# dsky_md_4_0v.net
KiCad netlist of a schematic drawn in EAGLE
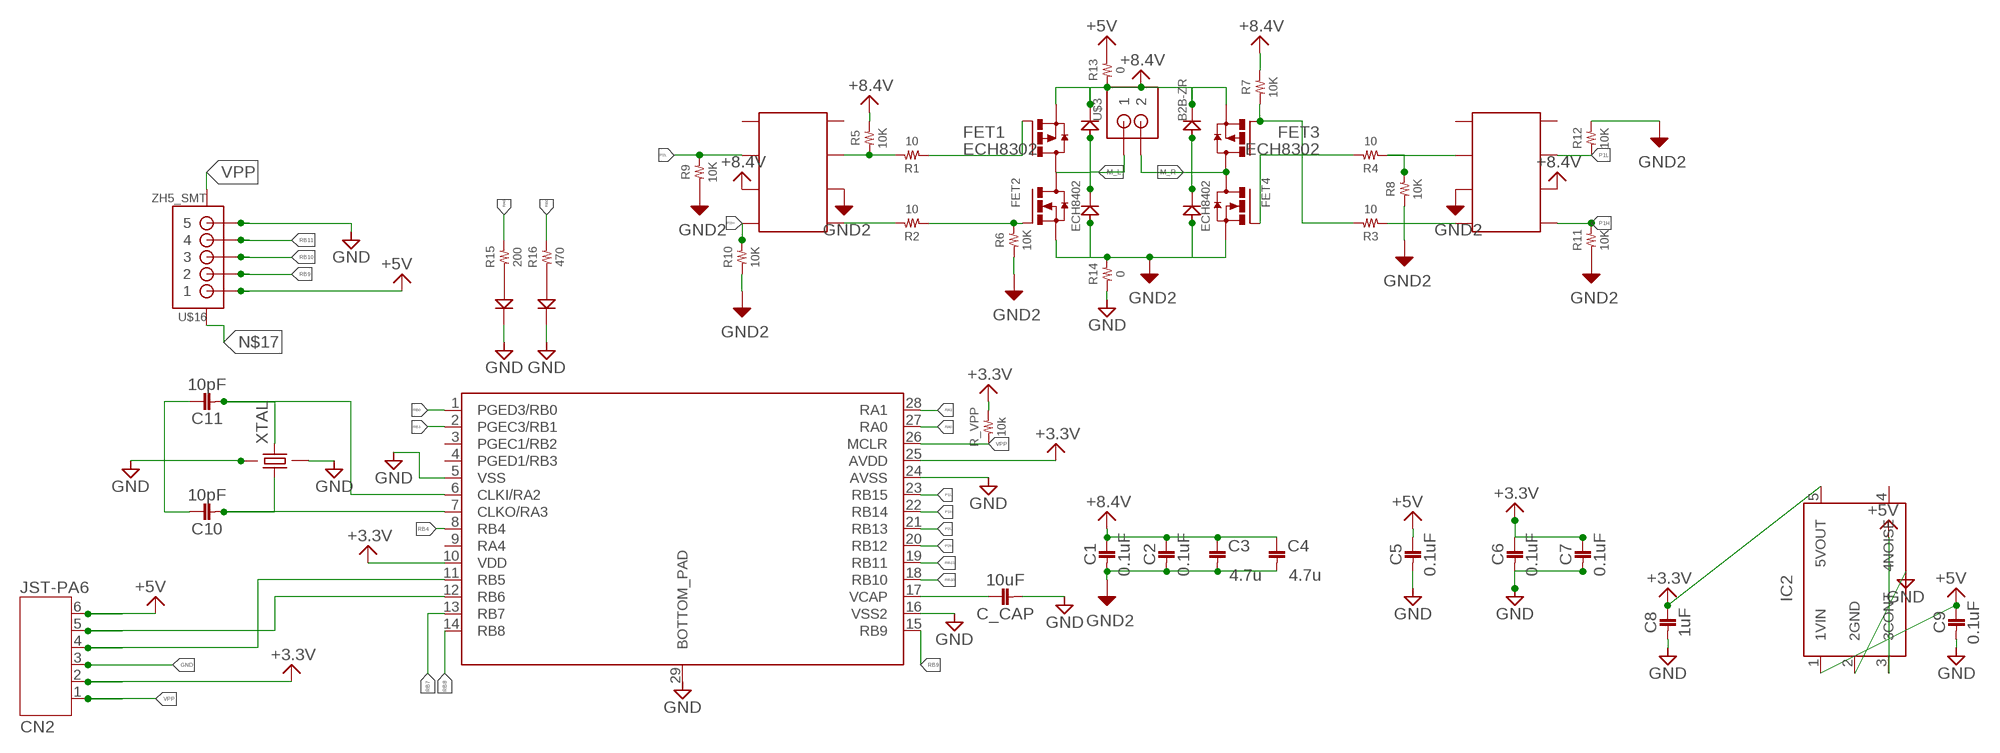
[diagram p0: schematic, sheet 1]

(export (version "E")
  (design (tool "Eeschema 10.0.6"))
  (components
    (comp (ref "C1")
      (value "0.1uF")
      (footprint "eagle-import:1608")
      (libsource (lib "eagle-import") (part "1608"))
    )
    (comp (ref "C2")
      (value "0.1uF")
      (footprint "eagle-import:1608")
      (libsource (lib "eagle-import") (part "1608"))
    )
    (comp (ref "C3")
      (value "4.7u")
      (footprint "eagle-import:2012")
      (libsource (lib "eagle-import") (part "2012"))
    )
    (comp (ref "C4")
      (value "4.7u")
      (footprint "eagle-import:2012")
      (libsource (lib "eagle-import") (part "2012"))
    )
    (comp (ref "C5")
      (value "0.1uF")
      (footprint "eagle-import:1608")
      (libsource (lib "eagle-import") (part "1608"))
    )
    (comp (ref "C6")
      (value "0.1uF")
      (footprint "eagle-import:1608")
      (libsource (lib "eagle-import") (part "1608"))
    )
    (comp (ref "C7")
      (value "0.1uF")
      (footprint "eagle-import:1608")
      (libsource (lib "eagle-import") (part "1608"))
    )
    (comp (ref "C8")
      (value "1uF")
      (footprint "eagle-import:1608")
      (libsource (lib "eagle-import") (part "1608"))
    )
    (comp (ref "C9")
      (value "0.1uF")
      (footprint "eagle-import:1608")
      (libsource (lib "eagle-import") (part "1608"))
    )
    (comp (ref "C10")
      (value "10pF")
      (footprint "eagle-import:1608")
      (libsource (lib "eagle-import") (part "1608"))
    )
    (comp (ref "C11")
      (value "10pF")
      (footprint "eagle-import:1608")
      (libsource (lib "eagle-import") (part "1608"))
    )
    (comp (ref "CN2")
      (value "JST-PA6")
      (footprint "eagle-import:JST-PA6")
      (libsource (lib "eagle-import") (part "JST-PA6"))
    )
    (comp (ref "C_CAP")
      (value "10uF")
      (footprint "eagle-import:1608")
      (libsource (lib "eagle-import") (part "1608"))
    )
    (comp (ref "D1")
      (value "SS2040")
      (footprint "eagle-import:SOD-123FL")
      (libsource (lib "eagle-import") (part "SS2040"))
    )
    (comp (ref "D2")
      (value "SS2040")
      (footprint "eagle-import:SOD-123FL")
      (libsource (lib "eagle-import") (part "SS2040"))
    )
    (comp (ref "D3")
      (value "SS2040")
      (footprint "eagle-import:SOD-123FL")
      (libsource (lib "eagle-import") (part "SS2040"))
    )
    (comp (ref "D4")
      (value "SS2040")
      (footprint "eagle-import:SOD-123FL")
      (libsource (lib "eagle-import") (part "SS2040"))
    )
    (comp (ref "FET1")
      (value "ECH8302")
      (footprint "eagle-import:ECH8")
      (libsource (lib "eagle-import") (part "ECH83"))
    )
    (comp (ref "FET2")
      (value "ECH8402")
      (footprint "eagle-import:ECH8")
      (libsource (lib "eagle-import") (part "ECH84"))
    )
    (comp (ref "FET3")
      (value "ECH8302")
      (footprint "eagle-import:ECH8")
      (libsource (lib "eagle-import") (part "ECH83"))
    )
    (comp (ref "FET4")
      (value "ECH8402")
      (footprint "eagle-import:ECH8")
      (libsource (lib "eagle-import") (part "ECH84"))
    )
    (comp (ref "IC1")
      (value "DSPIC33EP32MC202")
      (footprint "eagle-import:QFN-S28_6X6MC")
      (libsource (lib "eagle-import") (part "DSPIC33EP32MC202"))
    )
    (comp (ref "IC2")
      (value "NJM2866F33")
      (footprint "eagle-import:SSOP5-P-0.95")
      (libsource (lib "eagle-import") (part "TAR5SB"))
    )
    (comp (ref "IC3")
      (value "TC1427COA")
      (footprint "eagle-import:SOIC8")
      (libsource (lib "eagle-import") (part "TC1427COA"))
    )
    (comp (ref "IC4")
      (value "TC1427COA")
      (footprint "eagle-import:SOIC8")
      (libsource (lib "eagle-import") (part "TC1427COA"))
    )
    (comp (ref "LED1")
      (value "1608")
      (footprint "eagle-import:1608")
      (libsource (lib "eagle-import") (part "10_LED_1608"))
    )
    (comp (ref "LED2")
      (value "1608")
      (footprint "eagle-import:1608")
      (libsource (lib "eagle-import") (part "10_LED_1608"))
    )
    (comp (ref "R1")
      (value "10")
      (footprint "eagle-import:1608")
      (libsource (lib "eagle-import") (part "RESISTOR__SMD"))
    )
    (comp (ref "R2")
      (value "10")
      (footprint "eagle-import:1608")
      (libsource (lib "eagle-import") (part "RESISTOR__SMD"))
    )
    (comp (ref "R3")
      (value "10")
      (footprint "eagle-import:1608")
      (libsource (lib "eagle-import") (part "RESISTOR__SMD"))
    )
    (comp (ref "R4")
      (value "10")
      (footprint "eagle-import:1608")
      (libsource (lib "eagle-import") (part "RESISTOR__SMD"))
    )
    (comp (ref "R5")
      (value "10K")
      (footprint "eagle-import:1608")
      (libsource (lib "eagle-import") (part "RESISTOR__SMD"))
    )
    (comp (ref "R6")
      (value "10K")
      (footprint "eagle-import:1608")
      (libsource (lib "eagle-import") (part "RESISTOR__SMD"))
    )
    (comp (ref "R7")
      (value "10K")
      (footprint "eagle-import:1608")
      (libsource (lib "eagle-import") (part "RESISTOR__SMD"))
    )
    (comp (ref "R8")
      (value "10K")
      (footprint "eagle-import:1608")
      (libsource (lib "eagle-import") (part "RESISTOR__SMD"))
    )
    (comp (ref "R9")
      (value "10K")
      (footprint "eagle-import:1608")
      (libsource (lib "eagle-import") (part "RESISTOR__SMD"))
    )
    (comp (ref "R10")
      (value "10K")
      (footprint "eagle-import:1608")
      (libsource (lib "eagle-import") (part "RESISTOR__SMD"))
    )
    (comp (ref "R11")
      (value "10K")
      (footprint "eagle-import:1608")
      (libsource (lib "eagle-import") (part "RESISTOR__SMD"))
    )
    (comp (ref "R12")
      (value "10K")
      (footprint "eagle-import:1608")
      (libsource (lib "eagle-import") (part "RESISTOR__SMD"))
    )
    (comp (ref "R13")
      (value "0")
      (footprint "eagle-import:1608")
      (libsource (lib "eagle-import") (part "RESISTOR__SMD"))
    )
    (comp (ref "R14")
      (value "0")
      (footprint "eagle-import:1608")
      (libsource (lib "eagle-import") (part "RESISTOR__SMD"))
    )
    (comp (ref "R15")
      (value "200")
      (footprint "eagle-import:1608")
      (libsource (lib "eagle-import") (part "RESISTOR__SMD"))
    )
    (comp (ref "R16")
      (value "470")
      (footprint "eagle-import:1608")
      (libsource (lib "eagle-import") (part "RESISTOR__SMD"))
    )
    (comp (ref "R_VPP")
      (value "10k")
      (footprint "eagle-import:1608")
      (libsource (lib "eagle-import") (part "RESISTOR__SMD"))
    )
    (comp (ref "U$3")
      (value "B2B-ZR")
      (footprint "eagle-import:B2B-ZR")
      (libsource (lib "eagle-import") (part "B2B-ZR"))
    )
    (comp (ref "U$16")
      (value "ZH5_SMT")
      (footprint "eagle-import:ZH5_SMT")
      (libsource (lib "eagle-import") (part "ZH5_SMT"))
    )
    (comp (ref "XTAL")
      (value "X22")
      (footprint "eagle-import:SMD_X22")
      (libsource (lib "eagle-import") (part "X22"))
    )
  )
  (nets
    (net (code "1") (name "+3.3V") (class "Default")
      (node (ref "C6") (pin "P$1") (pinfunction "1_P$1") (pintype "passive"))
      (node (ref "C7") (pin "P$1") (pinfunction "1_P$1") (pintype "passive"))
      (node (ref "C8") (pin "P$1") (pinfunction "1_P$1") (pintype "passive"))
      (node (ref "CN2") (pin "2") (pinfunction "2_2") (pintype "passive"))
      (node (ref "IC1") (pin "10") (pinfunction "VDD_10") (pintype "bidirectional"))
      (node (ref "IC1") (pin "25") (pinfunction "AVDD_25") (pintype "bidirectional"))
      (node (ref "IC2") (pin "5") (pinfunction "5VOUT_5") (pintype "bidirectional"))
      (node (ref "R_VPP") (pin "2") (pinfunction "P$2_2") (pintype "passive"))
    )
    (net (code "2") (name "+5V") (class "Default")
      (node (ref "C5") (pin "P$1") (pinfunction "1_P$1") (pintype "passive"))
      (node (ref "C9") (pin "P$1") (pinfunction "1_P$1") (pintype "passive"))
      (node (ref "CN2") (pin "6") (pinfunction "6_6") (pintype "passive"))
      (node (ref "IC2") (pin "1") (pinfunction "1VIN_1") (pintype "bidirectional"))
      (node (ref "IC2") (pin "3") (pinfunction "3CONT_3") (pintype "bidirectional"))
      (node (ref "R13") (pin "2") (pinfunction "P$2_2") (pintype "passive"))
      (node (ref "U$16") (pin "P1") (pinfunction "1_P1") (pintype "bidirectional"))
    )
    (net (code "3") (name "+8.4V") (class "Default")
      (node (ref "C1") (pin "P$1") (pinfunction "1_P$1") (pintype "passive"))
      (node (ref "C2") (pin "P$1") (pinfunction "1_P$1") (pintype "passive"))
      (node (ref "C3") (pin "1") (pinfunction "1_1") (pintype "passive"))
      (node (ref "C4") (pin "1") (pinfunction "1_1") (pintype "passive"))
      (node (ref "D1") (pin "2") (pinfunction "PK_2") (pintype "bidirectional"))
      (node (ref "D3") (pin "2") (pinfunction "PK_2") (pintype "bidirectional"))
      (node (ref "FET1") (pin "1") (pinfunction "S_1") (pintype "passive"))
      (node (ref "FET1") (pin "2") (pinfunction "S_2") (pintype "passive"))
      (node (ref "FET1") (pin "3") (pinfunction "S_3") (pintype "passive"))
      (node (ref "FET3") (pin "1") (pinfunction "S_1") (pintype "passive"))
      (node (ref "FET3") (pin "2") (pinfunction "S_2") (pintype "passive"))
      (node (ref "FET3") (pin "3") (pinfunction "S_3") (pintype "passive"))
      (node (ref "IC3") (pin "3") (pinfunction "3_GND_3") (pintype "bidirectional"))
      (node (ref "IC4") (pin "3") (pinfunction "3_GND_3") (pintype "bidirectional"))
      (node (ref "R13") (pin "1") (pinfunction "P$1_1") (pintype "passive"))
      (node (ref "R5") (pin "2") (pinfunction "P$2_2") (pintype "passive"))
      (node (ref "R7") (pin "2") (pinfunction "P$2_2") (pintype "passive"))
    )
    (net (code "4") (name "GND") (class "Default")
      (node (ref "C10") (pin "P$1") (pinfunction "1_P$1") (pintype "passive"))
      (node (ref "C11") (pin "P$1") (pinfunction "1_P$1") (pintype "passive"))
      (node (ref "C5") (pin "P$2") (pinfunction "2_P$2") (pintype "passive"))
      (node (ref "C6") (pin "P$2") (pinfunction "2_P$2") (pintype "passive"))
      (node (ref "C7") (pin "P$2") (pinfunction "2_P$2") (pintype "passive"))
      (node (ref "C8") (pin "P$2") (pinfunction "2_P$2") (pintype "passive"))
      (node (ref "C9") (pin "P$2") (pinfunction "2_P$2") (pintype "passive"))
      (node (ref "CN2") (pin "3") (pinfunction "3_3") (pintype "passive"))
      (node (ref "C_CAP") (pin "P$2") (pinfunction "2_P$2") (pintype "passive"))
      (node (ref "IC1") (pin "16") (pinfunction "VSS2_16") (pintype "power_in"))
      (node (ref "IC1") (pin "24") (pinfunction "AVSS_24") (pintype "bidirectional"))
      (node (ref "IC1") (pin "29") (pinfunction "BOTTOM_PAD_29") (pintype "bidirectional"))
      (node (ref "IC1") (pin "5") (pinfunction "VSS_5") (pintype "power_in"))
      (node (ref "IC2") (pin "2") (pinfunction "2GND_2") (pintype "bidirectional"))
      (node (ref "LED1") (pin "2") (pinfunction "K_2") (pintype "bidirectional"))
      (node (ref "LED2") (pin "2") (pinfunction "K_2") (pintype "bidirectional"))
      (node (ref "R14") (pin "1") (pinfunction "P$1_1") (pintype "passive"))
      (node (ref "U$16") (pin "P5") (pinfunction "5_P5") (pintype "bidirectional"))
      (node (ref "XTAL") (pin "2") (pinfunction "2_2") (pintype "bidirectional"))
      (node (ref "XTAL") (pin "4") (pinfunction "4_4") (pintype "bidirectional"))
    )
    (net (code "5") (name "GND2") (class "Default")
      (node (ref "C1") (pin "P$2") (pinfunction "2_P$2") (pintype "passive"))
      (node (ref "C2") (pin "P$2") (pinfunction "2_P$2") (pintype "passive"))
      (node (ref "C3") (pin "2") (pinfunction "2_2") (pintype "passive"))
      (node (ref "C4") (pin "2") (pinfunction "2_2") (pintype "passive"))
      (node (ref "D2") (pin "1") (pinfunction "PA_1") (pintype "bidirectional"))
      (node (ref "D4") (pin "1") (pinfunction "PA_1") (pintype "bidirectional"))
      (node (ref "FET2") (pin "1") (pinfunction "S_1") (pintype "passive"))
      (node (ref "FET2") (pin "2") (pinfunction "S_2") (pintype "passive"))
      (node (ref "FET2") (pin "3") (pinfunction "S_3") (pintype "passive"))
      (node (ref "FET4") (pin "1") (pinfunction "S_1") (pintype "passive"))
      (node (ref "FET4") (pin "2") (pinfunction "S_2") (pintype "passive"))
      (node (ref "FET4") (pin "3") (pinfunction "S_3") (pintype "passive"))
      (node (ref "IC3") (pin "6") (pinfunction "6_VDD_6") (pintype "bidirectional"))
      (node (ref "IC4") (pin "6") (pinfunction "6_VDD_6") (pintype "bidirectional"))
      (node (ref "R10") (pin "1") (pinfunction "P$1_1") (pintype "passive"))
      (node (ref "R11") (pin "1") (pinfunction "P$1_1") (pintype "passive"))
      (node (ref "R12") (pin "2") (pinfunction "P$2_2") (pintype "passive"))
      (node (ref "R14") (pin "2") (pinfunction "P$2_2") (pintype "passive"))
      (node (ref "R6") (pin "1") (pinfunction "P$1_1") (pintype "passive"))
      (node (ref "R8") (pin "1") (pinfunction "P$1_1") (pintype "passive"))
      (node (ref "R9") (pin "1") (pinfunction "P$1_1") (pintype "passive"))
    )
    (net (code "6") (name "M_L") (class "Default")
      (node (ref "D1") (pin "1") (pinfunction "PA_1") (pintype "bidirectional"))
      (node (ref "D2") (pin "2") (pinfunction "PK_2") (pintype "bidirectional"))
      (node (ref "FET1") (pin "5") (pinfunction "D_5") (pintype "passive"))
      (node (ref "FET1") (pin "6") (pinfunction "D_6") (pintype "passive"))
      (node (ref "FET1") (pin "7") (pinfunction "D_7") (pintype "passive"))
      (node (ref "FET1") (pin "8") (pinfunction "D_8") (pintype "passive"))
      (node (ref "FET2") (pin "5") (pinfunction "D_5") (pintype "passive"))
      (node (ref "FET2") (pin "6") (pinfunction "D_6") (pintype "passive"))
      (node (ref "FET2") (pin "7") (pinfunction "D_7") (pintype "passive"))
      (node (ref "FET2") (pin "8") (pinfunction "D_8") (pintype "passive"))
      (node (ref "U$3") (pin "1") (pinfunction "1_1") (pintype "bidirectional"))
    )
    (net (code "7") (name "M_R") (class "Default")
      (node (ref "D3") (pin "1") (pinfunction "PA_1") (pintype "bidirectional"))
      (node (ref "D4") (pin "2") (pinfunction "PK_2") (pintype "bidirectional"))
      (node (ref "FET3") (pin "5") (pinfunction "D_5") (pintype "passive"))
      (node (ref "FET3") (pin "6") (pinfunction "D_6") (pintype "passive"))
      (node (ref "FET3") (pin "7") (pinfunction "D_7") (pintype "passive"))
      (node (ref "FET3") (pin "8") (pinfunction "D_8") (pintype "passive"))
      (node (ref "FET4") (pin "5") (pinfunction "D_5") (pintype "passive"))
      (node (ref "FET4") (pin "6") (pinfunction "D_6") (pintype "passive"))
      (node (ref "FET4") (pin "7") (pinfunction "D_7") (pintype "passive"))
      (node (ref "FET4") (pin "8") (pinfunction "D_8") (pintype "passive"))
      (node (ref "U$3") (pin "2") (pinfunction "2_2") (pintype "bidirectional"))
    )
    (net (code "8") (name "N$17") (class "Default")
      (node (ref "U$16") (pin "G1") (pinfunction "G_L_G1") (pintype "bidirectional"))
    )
    (net (code "9") (name "Net-(C10-2)") (class "Default")
      (node (ref "C10") (pin "P$2") (pinfunction "2_P$2") (pintype "passive"))
      (node (ref "IC1") (pin "7") (pinfunction "CLKO/RA3_7") (pintype "bidirectional"))
      (node (ref "XTAL") (pin "1") (pinfunction "1_1") (pintype "passive"))
    )
    (net (code "10") (name "Net-(C11-2)") (class "Default")
      (node (ref "C11") (pin "P$2") (pinfunction "2_P$2") (pintype "passive"))
      (node (ref "IC1") (pin "6") (pinfunction "CLKI/RA2_6") (pintype "bidirectional"))
      (node (ref "XTAL") (pin "3") (pinfunction "3_3") (pintype "passive"))
    )
    (net (code "11") (name "Net-(C_CAP-1)") (class "Default")
      (node (ref "C_CAP") (pin "P$1") (pinfunction "1_P$1") (pintype "passive"))
      (node (ref "IC1") (pin "17") (pinfunction "VCAP_17") (pintype "bidirectional"))
    )
    (net (code "12") (name "Net-(FET1-G)") (class "Default")
      (node (ref "FET1") (pin "4") (pinfunction "G_4") (pintype "passive"))
      (node (ref "R1") (pin "1") (pinfunction "P$1_1") (pintype "passive"))
    )
    (net (code "13") (name "Net-(FET2-G)") (class "Default")
      (node (ref "FET2") (pin "4") (pinfunction "G_4") (pintype "passive"))
      (node (ref "R2") (pin "1") (pinfunction "P$1_1") (pintype "passive"))
      (node (ref "R6") (pin "2") (pinfunction "P$2_2") (pintype "passive"))
    )
    (net (code "14") (name "Net-(FET3-G)") (class "Default")
      (node (ref "FET3") (pin "4") (pinfunction "G_4") (pintype "passive"))
      (node (ref "R3") (pin "2") (pinfunction "P$2_2") (pintype "passive"))
      (node (ref "R7") (pin "1") (pinfunction "P$1_1") (pintype "passive"))
    )
    (net (code "15") (name "Net-(FET4-G)") (class "Default")
      (node (ref "FET4") (pin "4") (pinfunction "G_4") (pintype "passive"))
      (node (ref "R4") (pin "2") (pinfunction "P$2_2") (pintype "passive"))
    )
    (net (code "16") (name "Net-(IC1-RB5)") (class "Default")
      (node (ref "CN2") (pin "4") (pinfunction "4_4") (pintype "passive"))
      (node (ref "IC1") (pin "11") (pinfunction "RB5_11") (pintype "bidirectional"))
    )
    (net (code "17") (name "Net-(IC1-RB6)") (class "Default")
      (node (ref "CN2") (pin "5") (pinfunction "5_5") (pintype "passive"))
      (node (ref "IC1") (pin "12") (pinfunction "RB6_12") (pintype "bidirectional"))
    )
    (net (code "18") (name "Net-(IC3-5_OUT_B)") (class "Default")
      (node (ref "IC3") (pin "5") (pinfunction "5_OUT_B_5") (pintype "bidirectional"))
      (node (ref "R2") (pin "2") (pinfunction "P$2_2") (pintype "passive"))
    )
    (net (code "19") (name "Net-(IC3-7_OUT_A)") (class "Default")
      (node (ref "IC3") (pin "7") (pinfunction "7_OUT_A_7") (pintype "bidirectional"))
      (node (ref "R1") (pin "2") (pinfunction "P$2_2") (pintype "passive"))
      (node (ref "R5") (pin "1") (pinfunction "P$1_1") (pintype "passive"))
    )
    (net (code "20") (name "Net-(IC4-5_OUT_B)") (class "Default")
      (node (ref "IC4") (pin "5") (pinfunction "5_OUT_B_5") (pintype "bidirectional"))
      (node (ref "R3") (pin "1") (pinfunction "P$1_1") (pintype "passive"))
    )
    (net (code "21") (name "Net-(IC4-7_OUT_A)") (class "Default")
      (node (ref "IC4") (pin "7") (pinfunction "7_OUT_A_7") (pintype "bidirectional"))
      (node (ref "R4") (pin "1") (pinfunction "P$1_1") (pintype "passive"))
      (node (ref "R8") (pin "2") (pinfunction "P$2_2") (pintype "passive"))
    )
    (net (code "22") (name "Net-(LED1-A)") (class "Default")
      (node (ref "LED1") (pin "1") (pinfunction "A_1") (pintype "bidirectional"))
      (node (ref "R15") (pin "1") (pinfunction "P$1_1") (pintype "passive"))
    )
    (net (code "23") (name "Net-(LED2-A)") (class "Default")
      (node (ref "LED2") (pin "1") (pinfunction "A_1") (pintype "bidirectional"))
      (node (ref "R16") (pin "1") (pinfunction "P$1_1") (pintype "passive"))
    )
    (net (code "24") (name "P1H") (class "Default")
      (node (ref "IC1") (pin "22") (pinfunction "RB14_22") (pintype "bidirectional"))
      (node (ref "IC4") (pin "4") (pinfunction "4_IN_B_4") (pintype "bidirectional"))
      (node (ref "R11") (pin "2") (pinfunction "P$2_2") (pintype "passive"))
    )
    (net (code "25") (name "P1L") (class "Default")
      (node (ref "IC1") (pin "23") (pinfunction "RB15_23") (pintype "bidirectional"))
      (node (ref "IC4") (pin "2") (pinfunction "2_IN_A_2") (pintype "bidirectional"))
      (node (ref "R12") (pin "1") (pinfunction "P$1_1") (pintype "passive"))
    )
    (net (code "26") (name "P2H") (class "Default")
      (node (ref "IC1") (pin "20") (pinfunction "RB12_20") (pintype "bidirectional"))
      (node (ref "IC3") (pin "4") (pinfunction "4_IN_B_4") (pintype "bidirectional"))
      (node (ref "R10") (pin "2") (pinfunction "P$2_2") (pintype "passive"))
    )
    (net (code "27") (name "P2L") (class "Default")
      (node (ref "IC1") (pin "21") (pinfunction "RB13_21") (pintype "bidirectional"))
      (node (ref "IC3") (pin "2") (pinfunction "2_IN_A_2") (pintype "bidirectional"))
      (node (ref "R9") (pin "2") (pinfunction "P$2_2") (pintype "passive"))
    )
    (net (code "28") (name "RA0") (class "Default")
      (node (ref "IC1") (pin "27") (pinfunction "RA0_27") (pintype "bidirectional"))
      (node (ref "R15") (pin "2") (pinfunction "P$2_2") (pintype "passive"))
    )
    (net (code "29") (name "RA1") (class "Default")
      (node (ref "IC1") (pin "28") (pinfunction "RA1_28") (pintype "bidirectional"))
    )
    (net (code "30") (name "RB0") (class "Default")
      (node (ref "IC1") (pin "1") (pinfunction "PGED3/RB0_1") (pintype "bidirectional"))
      (node (ref "R16") (pin "2") (pinfunction "P$2_2") (pintype "passive"))
    )
    (net (code "31") (name "RB1") (class "Default")
      (node (ref "IC1") (pin "2") (pinfunction "PGEC3/RB1_2") (pintype "bidirectional"))
    )
    (net (code "32") (name "RB4") (class "Default")
      (node (ref "IC1") (pin "8") (pinfunction "RB4_8") (pintype "bidirectional"))
    )
    (net (code "33") (name "RB7") (class "Default")
      (node (ref "IC1") (pin "13") (pinfunction "RB7_13") (pintype "bidirectional"))
    )
    (net (code "34") (name "RB8") (class "Default")
      (node (ref "IC1") (pin "14") (pinfunction "RB8_14") (pintype "bidirectional"))
    )
    (net (code "35") (name "RB9") (class "Default")
      (node (ref "IC1") (pin "15") (pinfunction "RB9_15") (pintype "bidirectional"))
      (node (ref "U$16") (pin "P2") (pinfunction "2_P2") (pintype "bidirectional"))
    )
    (net (code "36") (name "RB10") (class "Default")
      (node (ref "IC1") (pin "18") (pinfunction "RB10_18") (pintype "bidirectional"))
      (node (ref "U$16") (pin "P3") (pinfunction "3_P3") (pintype "bidirectional"))
    )
    (net (code "37") (name "RB11") (class "Default")
      (node (ref "IC1") (pin "19") (pinfunction "RB11_19") (pintype "bidirectional"))
      (node (ref "U$16") (pin "P4") (pinfunction "4_P4") (pintype "bidirectional"))
    )
    (net (code "38") (name "VPP") (class "Default")
      (node (ref "CN2") (pin "1") (pinfunction "1_1") (pintype "passive"))
      (node (ref "IC1") (pin "26") (pinfunction "MCLR_26") (pintype "bidirectional"))
      (node (ref "R_VPP") (pin "1") (pinfunction "P$1_1") (pintype "passive"))
      (node (ref "U$16") (pin "G2") (pinfunction "G_R_G2") (pintype "bidirectional"))
    )
    (net (code "39") (name "unconnected-(IC1-PGEC1{slash}RB2-Pad3)") (class "Default")
      (node (ref "IC1") (pin "3") (pinfunction "PGEC1/RB2_3") (pintype "bidirectional"))
    )
    (net (code "40") (name "unconnected-(IC1-PGED1{slash}RB3-Pad4)") (class "Default")
      (node (ref "IC1") (pin "4") (pinfunction "PGED1/RB3_4") (pintype "bidirectional"))
    )
    (net (code "41") (name "unconnected-(IC1-RA4-Pad9)") (class "Default")
      (node (ref "IC1") (pin "9") (pinfunction "RA4_9") (pintype "bidirectional"))
    )
    (net (code "42") (name "unconnected-(IC2-4NOISE-Pad4)") (class "Default")
      (node (ref "IC2") (pin "4") (pinfunction "4NOISE_4") (pintype "bidirectional"))
    )
    (net (code "43") (name "unconnected-(IC3-1_NC-Pad1)") (class "Default")
      (node (ref "IC3") (pin "1") (pinfunction "1_NC_1") (pintype "bidirectional"))
    )
    (net (code "44") (name "unconnected-(IC3-8_NC-Pad8)") (class "Default")
      (node (ref "IC3") (pin "8") (pinfunction "8_NC_8") (pintype "bidirectional"))
    )
    (net (code "45") (name "unconnected-(IC4-1_NC-Pad1)") (class "Default")
      (node (ref "IC4") (pin "1") (pinfunction "1_NC_1") (pintype "bidirectional"))
    )
    (net (code "46") (name "unconnected-(IC4-8_NC-Pad8)") (class "Default")
      (node (ref "IC4") (pin "8") (pinfunction "8_NC_8") (pintype "bidirectional"))
    )
  )
)
